# Rotating_stand.net
KiCad netlist of a schematic drawn in EAGLE
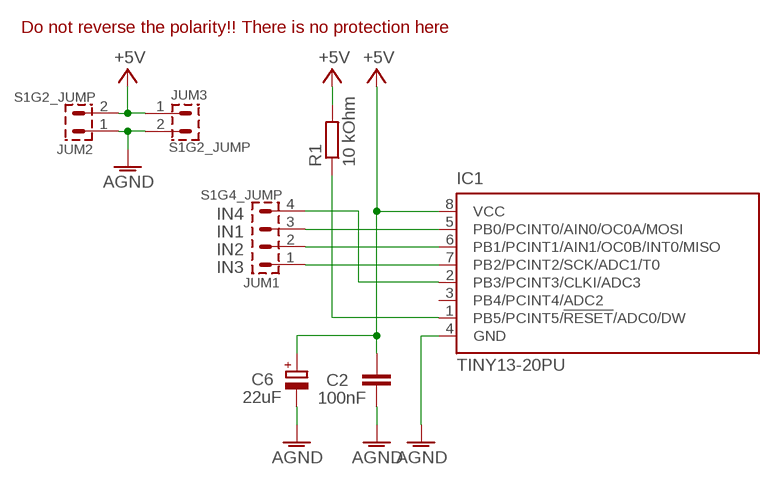
[diagram p0: schematic, sheet 1]

(export (version "E")
  (design (tool "Eeschema 10.0.6"))
  (components
    (comp (ref "C2")
      (value "100nF")
      (footprint "eagle-import:C050-024X044")
      (libsource (lib "eagle-import") (part "C-EU050-024X044"))
    )
    (comp (ref "C6")
      (value "22uF")
      (footprint "eagle-import:E2,5-5")
      (libsource (lib "eagle-import") (part "CPOL-EUE2.5-5"))
    )
    (comp (ref "IC1")
      (value "TINY13-20PU")
      (footprint "eagle-import:DIL08")
      (fields (field (name "MPN") "ATTINY13-20PU"))
      (libsource (lib "eagle-import") (part "TINY13PU-20"))
    )
    (comp (ref "JUM1")
      (value "S1G4_JUMP")
      (footprint "eagle-import:S1G4_JUM")
      (libsource (lib "eagle-import") (part "S1G4_JUMP"))
    )
    (comp (ref "JUM2")
      (value "S1G2_JUMP")
      (footprint "eagle-import:S1G2_JUM")
      (libsource (lib "eagle-import") (part "S1G2_JUMP"))
    )
    (comp (ref "JUM3")
      (value "S1G2_JUMP")
      (footprint "eagle-import:S1G2_JUM")
      (libsource (lib "eagle-import") (part "S1G2_JUMP"))
    )
    (comp (ref "R1")
      (value "10 kOhm")
      (footprint "eagle-import:0207_7")
      (libsource (lib "eagle-import") (part "R-EU_0207/7"))
    )
  )
  (nets
    (net (code "1") (name "+5V") (class "Default")
      (node (ref "C2") (pin "1") (pinfunction "1_1") (pintype "passive"))
      (node (ref "C6") (pin "+") (pinfunction "+_+") (pintype "passive"))
      (node (ref "IC1") (pin "8") (pinfunction "VCC_8") (pintype "power_in"))
      (node (ref "JUM2") (pin "2") (pinfunction "2_2") (pintype "passive"))
      (node (ref "JUM3") (pin "1") (pinfunction "1_1") (pintype "passive"))
      (node (ref "R1") (pin "2") (pinfunction "2_2") (pintype "passive"))
    )
    (net (code "2") (name "AGND") (class "Default")
      (node (ref "C2") (pin "2") (pinfunction "2_2") (pintype "passive"))
      (node (ref "C6") (pin "-") (pinfunction "-_-") (pintype "passive"))
      (node (ref "IC1") (pin "4") (pinfunction "GND_4") (pintype "power_in"))
      (node (ref "JUM2") (pin "1") (pinfunction "1_1") (pintype "passive"))
      (node (ref "JUM3") (pin "2") (pinfunction "2_2") (pintype "passive"))
    )
    (net (code "3") (name "Net-(IC1-PB0{slash}PCINT0{slash}AIN0{slash}OC0A{slash}MOSI)") (class "Default")
      (node (ref "IC1") (pin "5") (pinfunction "PB0/PCINT0/AIN0/OC0A/MOSI_5") (pintype "bidirectional"))
      (node (ref "JUM1") (pin "3") (pinfunction "3_3") (pintype "passive"))
    )
    (net (code "4") (name "Net-(IC1-PB1{slash}PCINT1{slash}AIN1{slash}OC0B{slash}INT0{slash}MISO)") (class "Default")
      (node (ref "IC1") (pin "6") (pinfunction "PB1/PCINT1/AIN1/OC0B/INT0/MISO_6") (pintype "bidirectional"))
      (node (ref "JUM1") (pin "2") (pinfunction "2_2") (pintype "passive"))
    )
    (net (code "5") (name "Net-(IC1-PB2{slash}PCINT2{slash}SCK{slash}ADC1{slash}T0)") (class "Default")
      (node (ref "IC1") (pin "7") (pinfunction "PB2/PCINT2/SCK/ADC1/T0_7") (pintype "bidirectional"))
      (node (ref "JUM1") (pin "1") (pinfunction "1_1") (pintype "passive"))
    )
    (net (code "6") (name "Net-(IC1-PB3{slash}PCINT3{slash}CLKI{slash}ADC3)") (class "Default")
      (node (ref "IC1") (pin "2") (pinfunction "PB3/PCINT3/CLKI/ADC3_2") (pintype "bidirectional"))
      (node (ref "JUM1") (pin "4") (pinfunction "4_4") (pintype "passive"))
    )
    (net (code "7") (name "Net-(IC1-PB5{slash}PCINT5{slash}~{RESET}{slash}ADC0{slash}DW)") (class "Default")
      (node (ref "IC1") (pin "1") (pinfunction "PB5/PCINT5/~{RESET}/ADC0/DW_1") (pintype "bidirectional"))
      (node (ref "R1") (pin "1") (pinfunction "1_1") (pintype "passive"))
    )
    (net (code "8") (name "unconnected-(IC1-PB4{slash}PCINT4{slash}ADC2-Pad3)") (class "Default")
      (node (ref "IC1") (pin "3") (pinfunction "PB4/PCINT4/ADC2_3") (pintype "bidirectional"))
    )
  )
)
